# InkTimeSlay.net
KiCad netlist of a schematic drawn in EAGLE
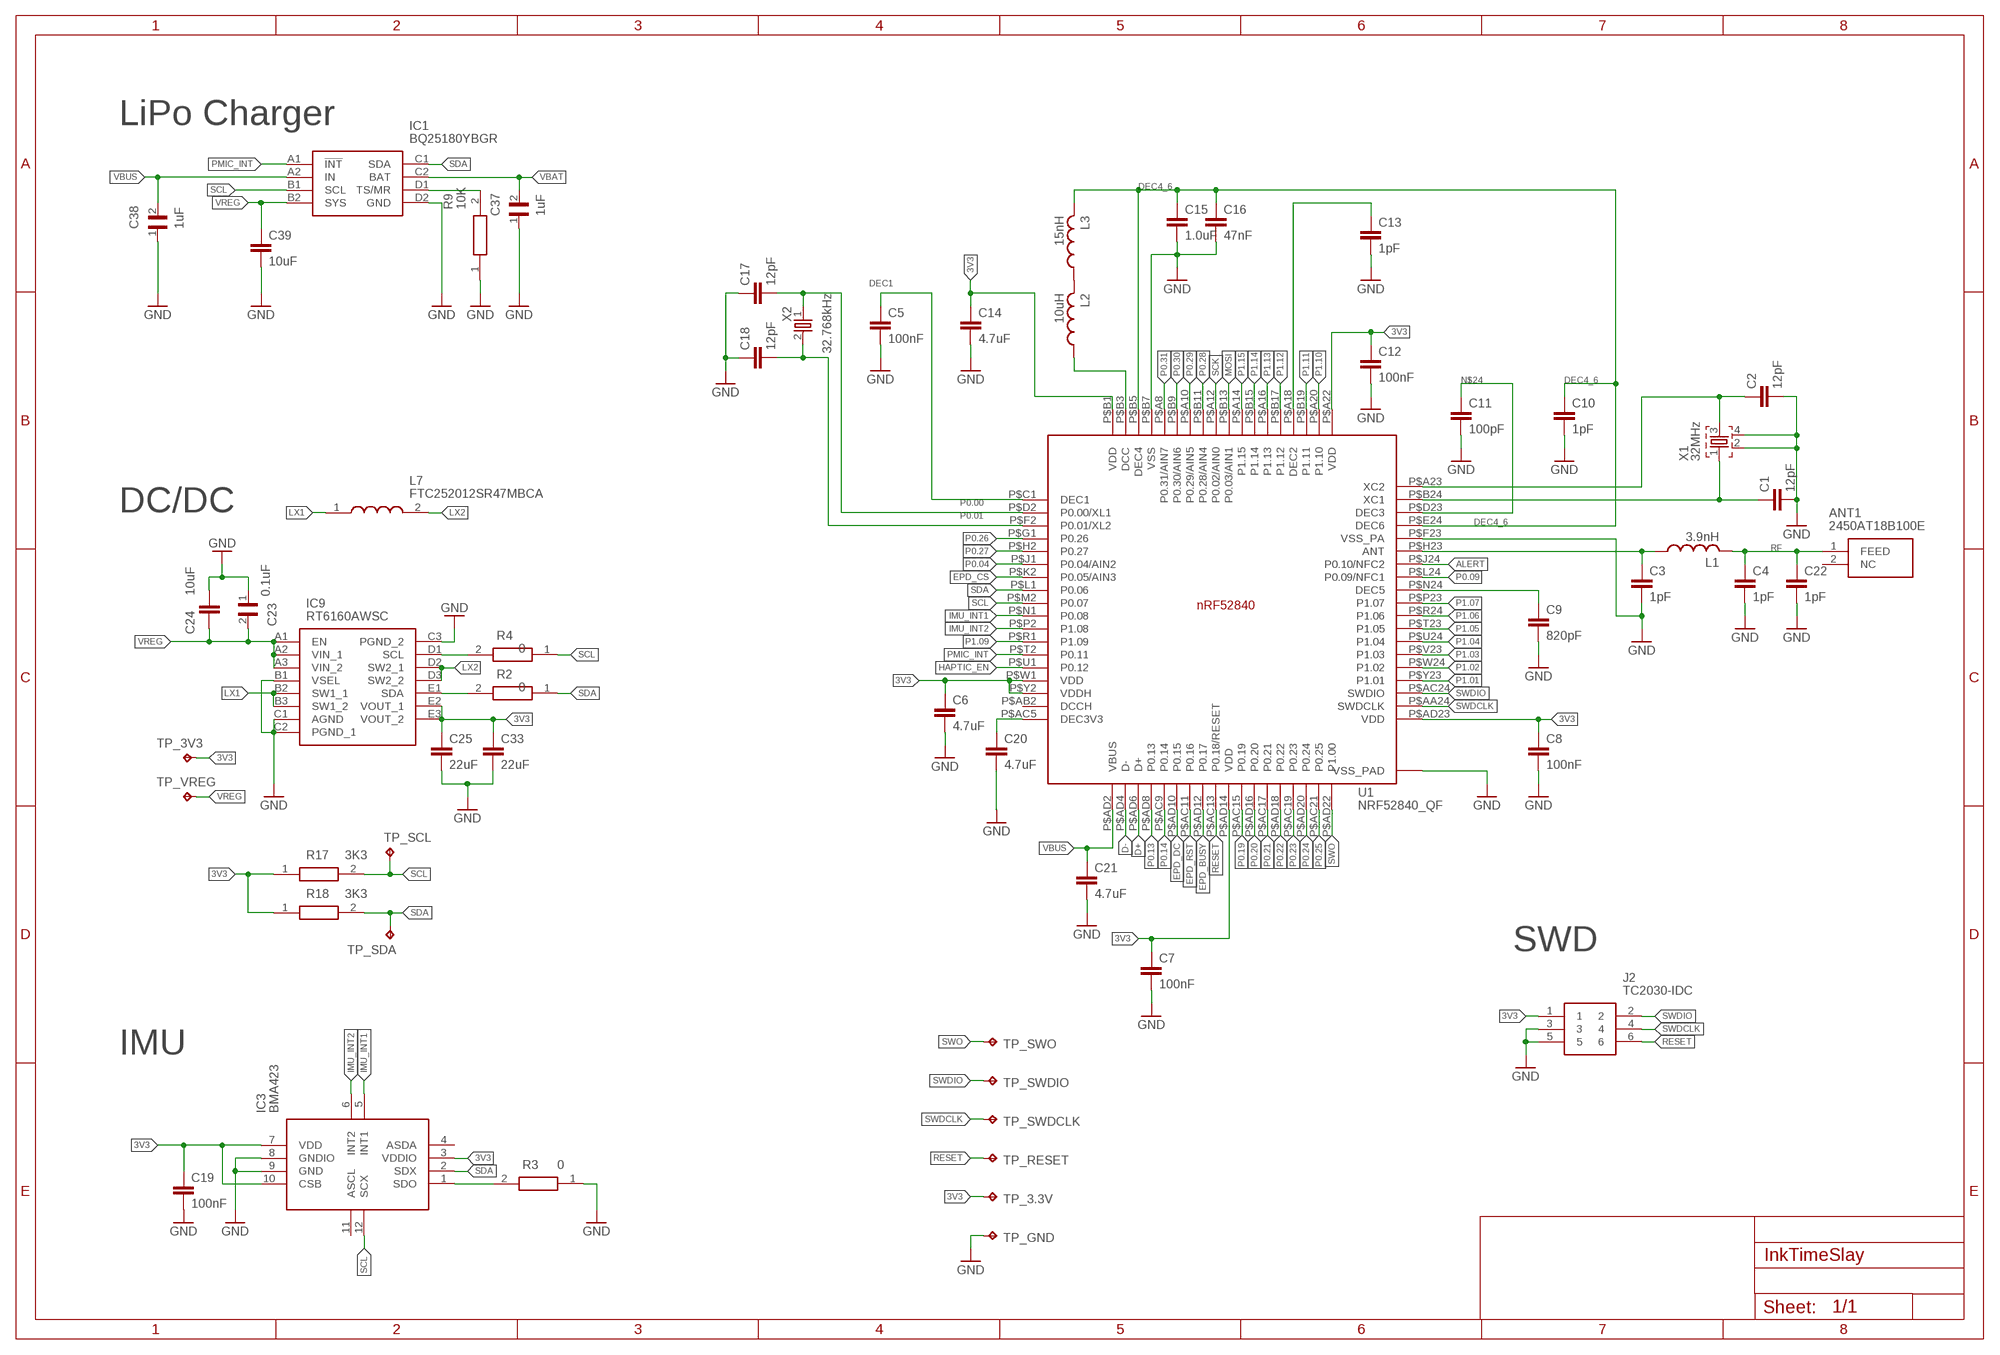
[diagram p0: schematic, sheet 1, part 1 of 2]
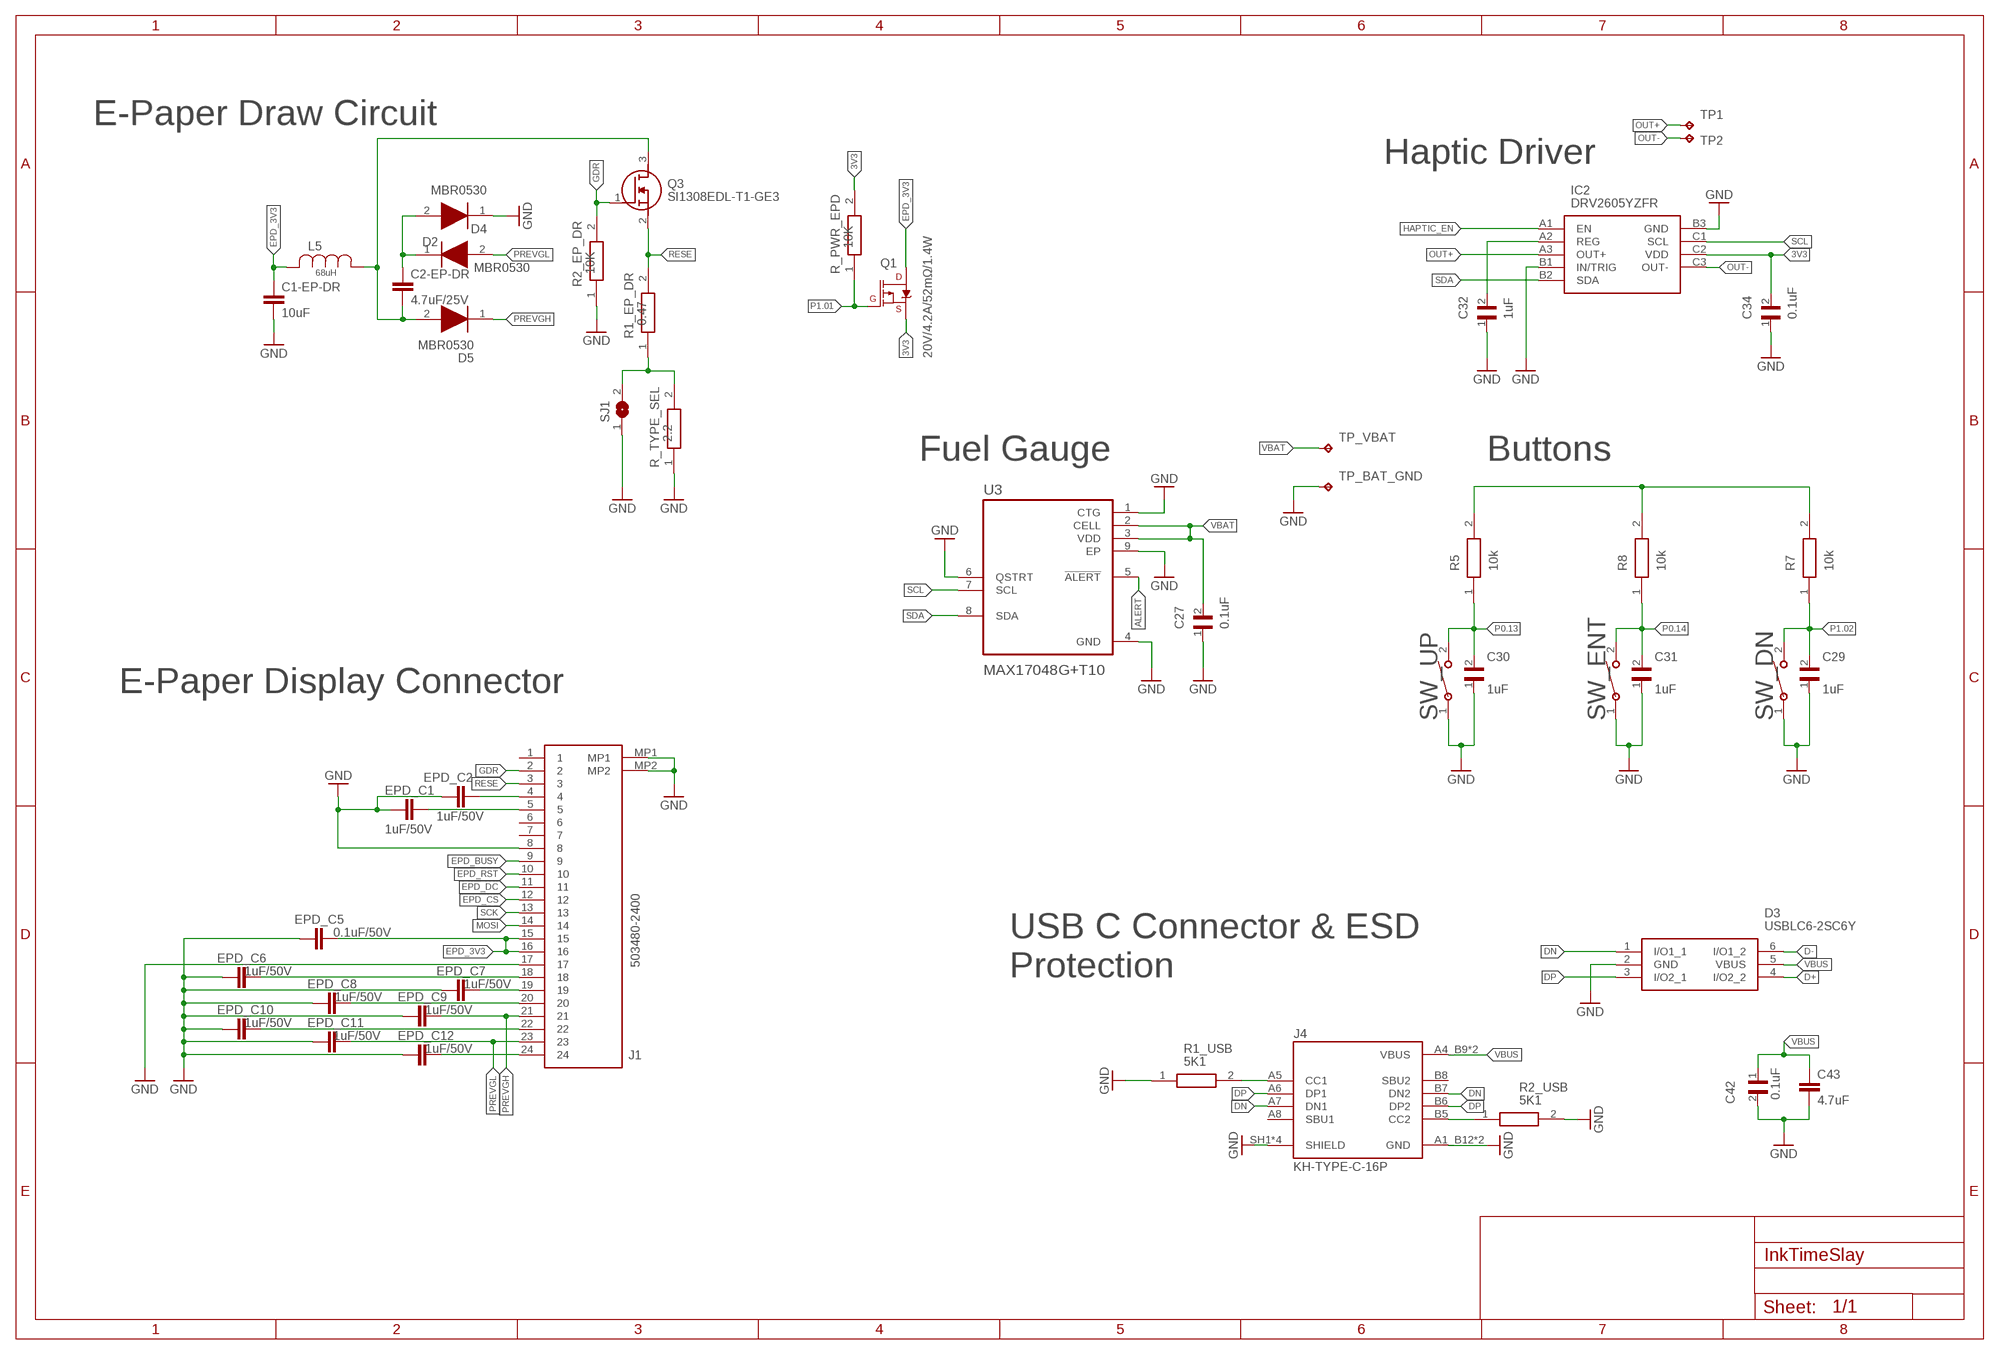
[diagram p1: schematic, sheet 1, part 2 of 2]

(export (version "E")
  (design (tool "Eeschema 10.0.6"))
  (components
    (comp (ref "ANT1")
      (value "2450AT18B100E")
      (footprint "eagle-import:2450AT18B100E_ANTC3216X140N")
      (fields (field (name "MOUSER_PART_NUMBER") "609-2450AT18B100E"))
      (libsource (lib "eagle-import") (part "2450AT18B100E_2450AT18B100E"))
    )
    (comp (ref "C1")
      (value "12pF")
      (footprint "eagle-import:NORDIC_NRF_3_RESC0201_L")
      (libsource (lib "eagle-import") (part "NORDIC_NRF_3_CAPACITOR_0201_L"))
    )
    (comp (ref "C1-EP-DR")
      (value "10uF")
      (footprint "eagle-import:NORDIC_NRF_3_RESC0402_L")
      (libsource (lib "eagle-import") (part "NORDIC_NRF_3_CAPACITOR_0402_L"))
    )
    (comp (ref "C2")
      (value "12pF")
      (footprint "eagle-import:NORDIC_NRF_3_RESC0201_L")
      (libsource (lib "eagle-import") (part "NORDIC_NRF_3_CAPACITOR_0201_L"))
    )
    (comp (ref "C2-EP-DR")
      (value "4.7uF/25V")
      (footprint "eagle-import:NORDIC_NRF_3_RESC0402_L")
      (libsource (lib "eagle-import") (part "NORDIC_NRF_3_CAPACITOR_0402_L"))
    )
    (comp (ref "C3")
      (value "1pF")
      (footprint "eagle-import:NORDIC_NRF_3_RESC0201_L")
      (libsource (lib "eagle-import") (part "NORDIC_NRF_3_CAPACITOR_0201_L"))
    )
    (comp (ref "C4")
      (value "1pF")
      (footprint "eagle-import:NORDIC_NRF_3_RESC0201_L")
      (libsource (lib "eagle-import") (part "NORDIC_NRF_3_CAPACITOR_0201_L"))
    )
    (comp (ref "C5")
      (value "100nF")
      (footprint "eagle-import:NORDIC_NRF_3_RESC0201_L")
      (libsource (lib "eagle-import") (part "NORDIC_NRF_3_CAPACITOR_0201_L"))
    )
    (comp (ref "C6")
      (value "4.7uF")
      (footprint "eagle-import:NORDIC_NRF_3_RESC0402_L")
      (libsource (lib "eagle-import") (part "NORDIC_NRF_3_CAPACITOR_0402_L"))
    )
    (comp (ref "C7")
      (value "100nF")
      (footprint "eagle-import:NORDIC_NRF_3_RESC0201_L")
      (libsource (lib "eagle-import") (part "NORDIC_NRF_3_CAPACITOR_0201_L"))
    )
    (comp (ref "C8")
      (value "100nF")
      (footprint "eagle-import:NORDIC_NRF_3_RESC0201_L")
      (libsource (lib "eagle-import") (part "NORDIC_NRF_3_CAPACITOR_0201_L"))
    )
    (comp (ref "C9")
      (value "820pF")
      (footprint "eagle-import:NORDIC_NRF_3_RESC0201_L")
      (libsource (lib "eagle-import") (part "NORDIC_NRF_3_CAPACITOR_0201_L"))
    )
    (comp (ref "C10")
      (value "1pF")
      (footprint "eagle-import:NORDIC_NRF_3_RESC0201_L")
      (libsource (lib "eagle-import") (part "NORDIC_NRF_3_CAPACITOR_0201_L"))
    )
    (comp (ref "C11")
      (value "100pF")
      (footprint "eagle-import:NORDIC_NRF_3_RESC0201_L")
      (libsource (lib "eagle-import") (part "NORDIC_NRF_3_CAPACITOR_0201_L"))
    )
    (comp (ref "C12")
      (value "100nF")
      (footprint "eagle-import:NORDIC_NRF_3_RESC0201_L")
      (libsource (lib "eagle-import") (part "NORDIC_NRF_3_CAPACITOR_0201_L"))
    )
    (comp (ref "C13")
      (value "1pF")
      (footprint "eagle-import:NORDIC_NRF_3_RESC0201_L")
      (libsource (lib "eagle-import") (part "NORDIC_NRF_3_CAPACITOR_0201_L"))
    )
    (comp (ref "C14")
      (value "4.7uF")
      (footprint "eagle-import:NORDIC_NRF_3_RESC0402_L")
      (libsource (lib "eagle-import") (part "NORDIC_NRF_3_CAPACITOR_0402_L"))
    )
    (comp (ref "C15")
      (value "1.0uF")
      (footprint "eagle-import:NORDIC_NRF_3_RESC0402_L")
      (libsource (lib "eagle-import") (part "NORDIC_NRF_3_CAPACITOR_0402_L"))
    )
    (comp (ref "C16")
      (value "47nF")
      (footprint "eagle-import:NORDIC_NRF_3_RESC0201_L")
      (libsource (lib "eagle-import") (part "NORDIC_NRF_3_CAPACITOR_0201_L"))
    )
    (comp (ref "C17")
      (value "12pF")
      (footprint "eagle-import:NORDIC_NRF_3_RESC0201_L")
      (libsource (lib "eagle-import") (part "NORDIC_NRF_3_CAPACITOR_0201_L"))
    )
    (comp (ref "C18")
      (value "12pF")
      (footprint "eagle-import:NORDIC_NRF_3_RESC0201_L")
      (libsource (lib "eagle-import") (part "NORDIC_NRF_3_CAPACITOR_0201_L"))
    )
    (comp (ref "C19")
      (value "100nF")
      (footprint "eagle-import:NORDIC_NRF_3_RESC0201_L")
      (libsource (lib "eagle-import") (part "NORDIC_NRF_3_CAPACITOR_0201_L"))
    )
    (comp (ref "C20")
      (value "4.7uF")
      (footprint "eagle-import:NORDIC_NRF_3_RESC0402_L")
      (libsource (lib "eagle-import") (part "NORDIC_NRF_3_CAPACITOR_0402_L"))
    )
    (comp (ref "C21")
      (value "4.7uF")
      (footprint "eagle-import:NORDIC_NRF_3_RESC0402_L")
      (libsource (lib "eagle-import") (part "NORDIC_NRF_3_CAPACITOR_0402_L"))
    )
    (comp (ref "C22")
      (value "1pF")
      (footprint "eagle-import:NORDIC_NRF_3_RESC0201_L")
      (libsource (lib "eagle-import") (part "NORDIC_NRF_3_CAPACITOR_0201_L"))
    )
    (comp (ref "C23")
      (value "0.1uF")
      (footprint "eagle-import:GRM011R60J152KE01L_2_CAPC0201X13N")
      (fields (field (name "MF") "Murata") (field (name "MP") "GRM011R60J152KE01L"))
      (libsource (lib "eagle-import") (part "GRM011R60J152KE01L_2_GRM011R60J152KE01L"))
    )
    (comp (ref "C24")
      (value "10uF")
      (footprint "eagle-import:NORDIC_NRF_3_RESC0402_L")
      (libsource (lib "eagle-import") (part "NORDIC_NRF_3_CAPACITOR_0402_L"))
    )
    (comp (ref "C25")
      (value "22uF")
      (footprint "eagle-import:NORDIC_NRF_3_RESC0402_L")
      (libsource (lib "eagle-import") (part "NORDIC_NRF_3_CAPACITOR_0402_L"))
    )
    (comp (ref "C27")
      (value "0.1uF")
      (footprint "eagle-import:GRM011R60J152KE01L_2_CAPC0201X13N")
      (fields (field (name "MF") "Murata") (field (name "MP") "GRM011R60J152KE01L"))
      (libsource (lib "eagle-import") (part "GRM011R60J152KE01L_2_GRM011R60J152KE01L"))
    )
    (comp (ref "C29")
      (value "1uF")
      (footprint "eagle-import:GRM011R60J152KE01L_2_CAPC0201X13N")
      (fields (field (name "MF") "Murata") (field (name "MP") "GRM011R60J152KE01L"))
      (libsource (lib "eagle-import") (part "GRM011R60J152KE01L_2_GRM011R60J152KE01L"))
    )
    (comp (ref "C30")
      (value "1uF")
      (footprint "eagle-import:GRM011R60J152KE01L_2_CAPC0201X13N")
      (fields (field (name "MF") "Murata") (field (name "MP") "GRM011R60J152KE01L"))
      (libsource (lib "eagle-import") (part "GRM011R60J152KE01L_2_GRM011R60J152KE01L"))
    )
    (comp (ref "C31")
      (value "1uF")
      (footprint "eagle-import:GRM011R60J152KE01L_2_CAPC0201X13N")
      (fields (field (name "MF") "Murata") (field (name "MP") "GRM011R60J152KE01L"))
      (libsource (lib "eagle-import") (part "GRM011R60J152KE01L_2_GRM011R60J152KE01L"))
    )
    (comp (ref "C32")
      (value "1uF")
      (footprint "eagle-import:GRM011R60J152KE01L_2_CAPC0201X13N")
      (fields (field (name "MF") "Murata") (field (name "MP") "GRM011R60J152KE01L"))
      (libsource (lib "eagle-import") (part "GRM011R60J152KE01L_2_GRM011R60J152KE01L"))
    )
    (comp (ref "C33")
      (value "22uF")
      (footprint "eagle-import:NORDIC_NRF_3_RESC0402_L")
      (libsource (lib "eagle-import") (part "NORDIC_NRF_3_CAPACITOR_0402_L"))
    )
    (comp (ref "C34")
      (value "0.1uF")
      (footprint "eagle-import:GRM011R60J152KE01L_2_CAPC0201X13N")
      (fields (field (name "MF") "Murata") (field (name "MP") "GRM011R60J152KE01L"))
      (libsource (lib "eagle-import") (part "GRM011R60J152KE01L_2_GRM011R60J152KE01L"))
    )
    (comp (ref "C37")
      (value "1uF")
      (footprint "eagle-import:GRM011R60J152KE01L_2_CAPC0201X13N")
      (fields (field (name "MF") "Murata") (field (name "MP") "GRM011R60J152KE01L"))
      (libsource (lib "eagle-import") (part "GRM011R60J152KE01L_2_GRM011R60J152KE01L"))
    )
    (comp (ref "C38")
      (value "1uF")
      (footprint "eagle-import:GRM011R60J152KE01L_2_CAPC0201X13N")
      (fields (field (name "MF") "Murata") (field (name "MP") "GRM011R60J152KE01L"))
      (libsource (lib "eagle-import") (part "GRM011R60J152KE01L_2_GRM011R60J152KE01L"))
    )
    (comp (ref "C39")
      (value "10uF")
      (footprint "eagle-import:NORDIC_NRF_3_RESC0402_L")
      (libsource (lib "eagle-import") (part "NORDIC_NRF_3_CAPACITOR_0402_L"))
    )
    (comp (ref "C42")
      (value "0.1uF")
      (footprint "eagle-import:GRM011R60J152KE01L_2_CAPC0201X13N")
      (fields (field (name "MF") "Murata") (field (name "MP") "GRM011R60J152KE01L"))
      (libsource (lib "eagle-import") (part "GRM011R60J152KE01L_2_GRM011R60J152KE01L"))
    )
    (comp (ref "C43")
      (value "4.7uF")
      (footprint "eagle-import:NORDIC_NRF_3_RESC0402_L")
      (libsource (lib "eagle-import") (part "NORDIC_NRF_3_CAPACITOR_0402_L"))
    )
    (comp (ref "D2")
      (value "MBR0530")
      (footprint "eagle-import:ESP32_C6_LIBRARY_5_SOD3716X135N")
      (fields (field (name "MF") "ON Semiconductor"))
      (libsource (lib "eagle-import") (part "ESP32_C6_LIBRARY_5_MBR0530"))
    )
    (comp (ref "D3")
      (value "USBLC6-2SC6Y")
      (footprint "eagle-import:ESP32_C6_LIBRARY_3_SOT95P280X145-6N")
      (fields (field (name "MF") "STMicroelectronics"))
      (libsource (lib "eagle-import") (part "ESP32_C6_LIBRARY_3_USBLC6-2SC6Y"))
    )
    (comp (ref "D4")
      (value "MBR0530")
      (footprint "eagle-import:ESP32_C6_LIBRARY_5_SOD3716X135N")
      (fields (field (name "MF") "ON Semiconductor"))
      (libsource (lib "eagle-import") (part "ESP32_C6_LIBRARY_5_MBR0530"))
    )
    (comp (ref "D5")
      (value "MBR0530")
      (footprint "eagle-import:ESP32_C6_LIBRARY_5_SOD3716X135N")
      (fields (field (name "MF") "ON Semiconductor"))
      (libsource (lib "eagle-import") (part "ESP32_C6_LIBRARY_5_MBR0530"))
    )
    (comp (ref "EPD_C1")
      (value "1uF/50V")
      (footprint "eagle-import:NORDIC_NRF_3_RESC0402_L")
      (libsource (lib "eagle-import") (part "NORDIC_NRF_3_CAPACITOR_0402_L"))
    )
    (comp (ref "EPD_C2")
      (value "1uF/50V")
      (footprint "eagle-import:NORDIC_NRF_3_RESC0402_L")
      (libsource (lib "eagle-import") (part "NORDIC_NRF_3_CAPACITOR_0402_L"))
    )
    (comp (ref "EPD_C5")
      (value "0.1uF/50V")
      (footprint "eagle-import:NORDIC_NRF_3_RESC0201_L")
      (libsource (lib "eagle-import") (part "NORDIC_NRF_3_CAPACITOR_0201_L"))
    )
    (comp (ref "EPD_C6")
      (value "1uF/50V")
      (footprint "eagle-import:NORDIC_NRF_3_RESC0402_L")
      (libsource (lib "eagle-import") (part "NORDIC_NRF_3_CAPACITOR_0402_L"))
    )
    (comp (ref "EPD_C7")
      (value "1uF/50V")
      (footprint "eagle-import:NORDIC_NRF_3_RESC0402_L")
      (libsource (lib "eagle-import") (part "NORDIC_NRF_3_CAPACITOR_0402_L"))
    )
    (comp (ref "EPD_C8")
      (value "1uF/50V")
      (footprint "eagle-import:NORDIC_NRF_3_RESC0402_L")
      (libsource (lib "eagle-import") (part "NORDIC_NRF_3_CAPACITOR_0402_L"))
    )
    (comp (ref "EPD_C9")
      (value "1uF/50V")
      (footprint "eagle-import:NORDIC_NRF_3_RESC0402_L")
      (libsource (lib "eagle-import") (part "NORDIC_NRF_3_CAPACITOR_0402_L"))
    )
    (comp (ref "EPD_C10")
      (value "1uF/50V")
      (footprint "eagle-import:NORDIC_NRF_3_RESC0402_L")
      (libsource (lib "eagle-import") (part "NORDIC_NRF_3_CAPACITOR_0402_L"))
    )
    (comp (ref "EPD_C11")
      (value "1uF/50V")
      (footprint "eagle-import:NORDIC_NRF_3_RESC0402_L")
      (libsource (lib "eagle-import") (part "NORDIC_NRF_3_CAPACITOR_0402_L"))
    )
    (comp (ref "EPD_C12")
      (value "1uF/50V")
      (footprint "eagle-import:NORDIC_NRF_3_RESC0402_L")
      (libsource (lib "eagle-import") (part "NORDIC_NRF_3_CAPACITOR_0402_L"))
    )
    (comp (ref "IC1")
      (value "BQ25180YBGR")
      (footprint "eagle-import:BQ25180YBGR_BGA8C40P2X4_100X155X50")
      (fields (field (name "MOUSER_PART_NUMBER") "595-BQ25180YBGR"))
      (libsource (lib "eagle-import") (part "BQ25180YBGR_BQ25180YBGR"))
    )
    (comp (ref "IC2")
      (value "DRV2605YZFR")
      (footprint "eagle-import:DRV2605YZFR_BGA9C50P3X3_144X144X62")
      (libsource (lib "eagle-import") (part "DRV2605YZFR_DRV2605YZFR"))
    )
    (comp (ref "IC3")
      (value "BMA423")
      (footprint "eagle-import:BMA423_BMA423")
      (fields (field (name "MOUSER_PART_NUMBER") "262-BMA423"))
      (libsource (lib "eagle-import") (part "BMA423_BMA423"))
    )
    (comp (ref "IC9")
      (value "RT6160AWSC")
      (footprint "eagle-import:RT6160AWSC_BGA15C40P3X5_140X230X60")
      (fields (field (name "MOUSER_PART_NUMBER") "835-RT6160AWSC"))
      (libsource (lib "eagle-import") (part "RT6160AWSC_RT6160AWSC"))
    )
    (comp (ref "J1")
      (value "503480-2400")
      (footprint "eagle-import:503480-2400_5034802400")
      (fields (field (name "MOUSER_PART_NUMBER") "538-503480-2400"))
      (libsource (lib "eagle-import") (part "503480-2400_503480-2400"))
    )
    (comp (ref "J2")
      (value "TC2030-IDC")
      (footprint "eagle-import:TC2030-IDC_TC2030IDC")
      (libsource (lib "eagle-import") (part "TC2030-IDC_TC2030-IDC"))
    )
    (comp (ref "J4")
      (value "KH-TYPE-C-16P")
      (footprint "eagle-import:KH-TYPE-C-16P_KINGHELM_KH-TYPE-C-16P")
      (fields (field (name "MF") "kinghelm"))
      (libsource (lib "eagle-import") (part "KH-TYPE-C-16P_KH-TYPE-C-16P"))
    )
    (comp (ref "L1")
      (value "3.9nH")
      (footprint "eagle-import:NORDIC_NRF_2_RESC0402_L")
      (libsource (lib "eagle-import") (part "NORDIC_NRF_2_INDUCTOR_0402_L"))
    )
    (comp (ref "L2")
      (value "10uH")
      (footprint "eagle-import:NORDIC_NRF_2_RESC0402_L")
      (libsource (lib "eagle-import") (part "NORDIC_NRF_2_INDUCTOR_0402_L"))
    )
    (comp (ref "L3")
      (value "15nH")
      (footprint "eagle-import:NORDIC_NRF_2_RESC0402_L")
      (libsource (lib "eagle-import") (part "NORDIC_NRF_2_INDUCTOR_0402_L"))
    )
    (comp (ref "L5")
      (value "68uH")
      (footprint "eagle-import:ESP32_C6_LIBRARY_2_IND_4828-WE-TPC_WRE")
      (fields
        (field (name "MANUFACTURER_PART_NUMBER") "744043680")
        (field (name "COPYRIGHT") "Copyright (C) 2024 Ultra Librarian. All rights reserved.")
      )
      (libsource (lib "eagle-import") (part "ESP32_C6_LIBRARY_2_744043680IND_4828-WE-TPC_WRE"))
    )
    (comp (ref "L7")
      (value "FTC252012SR47MBCA")
      (footprint "eagle-import:MLP2016SR47MT0S1_INDC2016X100N")
      (libsource (lib "eagle-import") (part "MLP2016SR47MT0S1_FTC252012SR47MBCA"))
    )
    (comp (ref "Q1")
      (value "20V/4.2A/52mΩ/1.4W")
      (footprint "eagle-import:ESP32_C6_LIBRARY_4_ESP32_C6_LIBRARY_4_ESP32_C6_LIBRARY_4_ESP32_C6_LIBRARY_4_ESP32_WROVER_SPARKFUN-DISCRETESEMI_SOT23-3")
      (libsource (lib "eagle-import") (part "ESP32_C6_LIBRARY_4_ESP32_WROVER_SPARKFUN-DISCRETESEMI_MOSFET_PCH-DMG2305UX-7"))
    )
    (comp (ref "Q3")
      (value "SI1308EDL-T1-GE3")
      (footprint "eagle-import:ESP32_C6_LIBRARY_6_SOT65P210X110-3N")
      (fields (field (name "MF") "Vishay Siliconix"))
      (libsource (lib "eagle-import") (part "ESP32_C6_LIBRARY_6_SI1308EDL-T1-GE3"))
    )
    (comp (ref "R1_EP_DR")
      (value "0.47")
      (footprint "eagle-import:ERA-1AEB3401C_0201")
      (libsource (lib "eagle-import") (part "ERA-1AEB3401C_CPF0201D7K68C1"))
    )
    (comp (ref "R1_USB")
      (value "5K1")
      (footprint "eagle-import:ERA-1AEB3401C_0201")
      (libsource (lib "eagle-import") (part "ERA-1AEB3401C_CPF0201D7K68C1"))
    )
    (comp (ref "R2")
      (value "0")
      (footprint "eagle-import:ERA-1AEB3401C_0201")
      (libsource (lib "eagle-import") (part "ERA-1AEB3401C_CPF0201D7K68C1"))
    )
    (comp (ref "R2_EP_DR")
      (value "10K")
      (footprint "eagle-import:ERA-1AEB3401C_0201")
      (libsource (lib "eagle-import") (part "ERA-1AEB3401C_CPF0201D7K68C1"))
    )
    (comp (ref "R2_USB")
      (value "5K1")
      (footprint "eagle-import:ERA-1AEB3401C_0201")
      (libsource (lib "eagle-import") (part "ERA-1AEB3401C_CPF0201D7K68C1"))
    )
    (comp (ref "R3")
      (value "0")
      (footprint "eagle-import:ERA-1AEB3401C_0201")
      (libsource (lib "eagle-import") (part "ERA-1AEB3401C_CPF0201D7K68C1"))
    )
    (comp (ref "R4")
      (value "0")
      (footprint "eagle-import:ERA-1AEB3401C_0201")
      (libsource (lib "eagle-import") (part "ERA-1AEB3401C_CPF0201D7K68C1"))
    )
    (comp (ref "R5")
      (value "10k")
      (footprint "eagle-import:ERA-1AEB3401C_0201")
      (libsource (lib "eagle-import") (part "ERA-1AEB3401C_CPF0201D7K68C1"))
    )
    (comp (ref "R7")
      (value "10k")
      (footprint "eagle-import:ERA-1AEB3401C_0201")
      (libsource (lib "eagle-import") (part "ERA-1AEB3401C_CPF0201D7K68C1"))
    )
    (comp (ref "R8")
      (value "10k")
      (footprint "eagle-import:ERA-1AEB3401C_0201")
      (libsource (lib "eagle-import") (part "ERA-1AEB3401C_CPF0201D7K68C1"))
    )
    (comp (ref "R9")
      (value "10K")
      (footprint "eagle-import:ERA-1AEB3401C_0201")
      (libsource (lib "eagle-import") (part "ERA-1AEB3401C_CPF0201D7K68C1"))
    )
    (comp (ref "R17")
      (value "3K3")
      (footprint "eagle-import:ERA-1AEB3401C_0201")
      (libsource (lib "eagle-import") (part "ERA-1AEB3401C_CPF0201D7K68C1"))
    )
    (comp (ref "R18")
      (value "3K3")
      (footprint "eagle-import:ERA-1AEB3401C_0201")
      (libsource (lib "eagle-import") (part "ERA-1AEB3401C_CPF0201D7K68C1"))
    )
    (comp (ref "R_PWR_EPD")
      (value "10K")
      (footprint "eagle-import:ERA-1AEB3401C_0201")
      (libsource (lib "eagle-import") (part "ERA-1AEB3401C_CPF0201D7K68C1"))
    )
    (comp (ref "R_TYPE_SEL")
      (value "2.2")
      (footprint "eagle-import:ERA-1AEB3401C_0201")
      (libsource (lib "eagle-import") (part "ERA-1AEB3401C_CPF0201D7K68C1"))
    )
    (comp (ref "SJ1")
      (value "ESP32_C6_LIBRARY_7_JUMPER_SJ")
      (footprint "eagle-import:ESP32_C6_LIBRARY_7_JUMPER_SJ")
      (libsource (lib "eagle-import") (part "ESP32_C6_LIBRARY_7_JUMPER_SJ"))
    )
    (comp (ref "SW_DN")
      (value "2025-10-22_07-23-44_LIBRARY_EVP-AKE31ASW_EVP-AKE31A_PAN")
      (footprint "eagle-import:2025-10-22_07-23-44_LIBRARY_SW_EVP-AKE31A_PAN")
      (fields
        (field (name "MANUFACTURER_PART_NUMBER") "EVP-AKE31A")
        (field (name "COPYRIGHT") "Copyright (C) 2025 Ultra Librarian. All rights reserved.")
      )
      (libsource (lib "eagle-import") (part "2025-10-22_07-23-44_LIBRARY_EVP-AKE31ASW_EVP-AKE31A_PAN"))
    )
    (comp (ref "SW_ENT")
      (value "2025-10-22_07-23-44_LIBRARY_EVP-AKE31ASW_EVP-AKE31A_PAN")
      (footprint "eagle-import:2025-10-22_07-23-44_LIBRARY_SW_EVP-AKE31A_PAN")
      (fields
        (field (name "MANUFACTURER_PART_NUMBER") "EVP-AKE31A")
        (field (name "COPYRIGHT") "Copyright (C) 2025 Ultra Librarian. All rights reserved.")
      )
      (libsource (lib "eagle-import") (part "2025-10-22_07-23-44_LIBRARY_EVP-AKE31ASW_EVP-AKE31A_PAN"))
    )
    (comp (ref "SW_UP")
      (value "2025-10-22_07-23-44_LIBRARY_EVP-AKE31ASW_EVP-AKE31A_PAN")
      (footprint "eagle-import:2025-10-22_07-23-44_LIBRARY_SW_EVP-AKE31A_PAN")
      (fields
        (field (name "MANUFACTURER_PART_NUMBER") "EVP-AKE31A")
        (field (name "COPYRIGHT") "Copyright (C) 2025 Ultra Librarian. All rights reserved.")
      )
      (libsource (lib "eagle-import") (part "2025-10-22_07-23-44_LIBRARY_EVP-AKE31ASW_EVP-AKE31A_PAN"))
    )
    (comp (ref "TP1")
      (value "HECTOR_WATCH_1_TPTP20R")
      (footprint "eagle-import:HECTOR_WATCH_1_TP20R")
      (libsource (lib "eagle-import") (part "HECTOR_WATCH_1_TPTP20R"))
    )
    (comp (ref "TP2")
      (value "HECTOR_WATCH_1_TPTP20R")
      (footprint "eagle-import:HECTOR_WATCH_1_TP20R")
      (libsource (lib "eagle-import") (part "HECTOR_WATCH_1_TPTP20R"))
    )
    (comp (ref "TP_3.3V")
      (value "HECTOR_WATCH_1_TPTP20R")
      (footprint "eagle-import:HECTOR_WATCH_1_TP20R")
      (libsource (lib "eagle-import") (part "HECTOR_WATCH_1_TPTP20R"))
    )
    (comp (ref "TP_3V3")
      (value "HECTOR_WATCH_1_TPTP20R")
      (footprint "eagle-import:HECTOR_WATCH_1_TP20R")
      (libsource (lib "eagle-import") (part "HECTOR_WATCH_1_TPTP20R"))
    )
    (comp (ref "TP_BAT_GND")
      (value "HECTOR_WATCH_1_TPTP20R")
      (footprint "eagle-import:HECTOR_WATCH_1_TP20R")
      (libsource (lib "eagle-import") (part "HECTOR_WATCH_1_TPTP20R"))
    )
    (comp (ref "TP_GND")
      (value "HECTOR_WATCH_1_TPTP20R")
      (footprint "eagle-import:HECTOR_WATCH_1_TP20R")
      (libsource (lib "eagle-import") (part "HECTOR_WATCH_1_TPTP20R"))
    )
    (comp (ref "TP_RESET")
      (value "HECTOR_WATCH_1_TPTP20R")
      (footprint "eagle-import:HECTOR_WATCH_1_TP20R")
      (libsource (lib "eagle-import") (part "HECTOR_WATCH_1_TPTP20R"))
    )
    (comp (ref "TP_SCL")
      (value "HECTOR_WATCH_1_TPTP20R")
      (footprint "eagle-import:HECTOR_WATCH_1_TP20R")
      (libsource (lib "eagle-import") (part "HECTOR_WATCH_1_TPTP20R"))
    )
    (comp (ref "TP_SDA")
      (value "HECTOR_WATCH_1_TPTP20R")
      (footprint "eagle-import:HECTOR_WATCH_1_TP20R")
      (libsource (lib "eagle-import") (part "HECTOR_WATCH_1_TPTP20R"))
    )
    (comp (ref "TP_SWDCLK")
      (value "HECTOR_WATCH_1_TPTP20R")
      (footprint "eagle-import:HECTOR_WATCH_1_TP20R")
      (libsource (lib "eagle-import") (part "HECTOR_WATCH_1_TPTP20R"))
    )
    (comp (ref "TP_SWDIO")
      (value "HECTOR_WATCH_1_TPTP20R")
      (footprint "eagle-import:HECTOR_WATCH_1_TP20R")
      (libsource (lib "eagle-import") (part "HECTOR_WATCH_1_TPTP20R"))
    )
    (comp (ref "TP_SWO")
      (value "HECTOR_WATCH_1_TPTP20R")
      (footprint "eagle-import:HECTOR_WATCH_1_TP20R")
      (libsource (lib "eagle-import") (part "HECTOR_WATCH_1_TPTP20R"))
    )
    (comp (ref "TP_VBAT")
      (value "HECTOR_WATCH_1_TPTP20R")
      (footprint "eagle-import:HECTOR_WATCH_1_TP20R")
      (libsource (lib "eagle-import") (part "HECTOR_WATCH_1_TPTP20R"))
    )
    (comp (ref "TP_VREG")
      (value "HECTOR_WATCH_1_TPTP20R")
      (footprint "eagle-import:HECTOR_WATCH_1_TP20R")
      (libsource (lib "eagle-import") (part "HECTOR_WATCH_1_TPTP20R"))
    )
    (comp (ref "U1")
      (value "NRF52840_QF")
      (footprint "eagle-import:NORDIC_NRF_4_AQFN50P700X700X85_HS-74N")
      (libsource (lib "eagle-import") (part "NORDIC_NRF_4_NRF52840_QF"))
    )
    (comp (ref "U3")
      (value "MAX17048G+T10")
      (footprint "eagle-import:ESP32_C6_LIBRARY_SON50P200X200X80-9N")
      (fields (field (name "MF") "Analog Devices"))
      (libsource (lib "eagle-import") (part "ESP32_C6_LIBRARY_MAX17048G+T10"))
    )
    (comp (ref "X1")
      (value "32MHz")
      (footprint "eagle-import:NORDIC_NRF_BT-XTAL_2016_N")
      (libsource (lib "eagle-import") (part "NORDIC_NRF_XTAL_32MHZ"))
    )
    (comp (ref "X2")
      (value "32.768kHz")
      (footprint "eagle-import:NORDIC_NRF_1_XTAL_3215_N")
      (libsource (lib "eagle-import") (part "NORDIC_NRF_1_XTAL_32KHZ"))
    )
  )
  (nets
    (net (code "1") (name "/DEC1") (class "Default")
      (node (ref "C5") (pin "1") (pinfunction "1_1") (pintype "passive"))
      (node (ref "U1") (pin "P$C1") (pinfunction "DEC1_P$C1") (pintype "power_in"))
    )
    (net (code "2") (name "/DEC4_6") (class "Default")
      (node (ref "C10") (pin "1") (pinfunction "1_1") (pintype "passive"))
      (node (ref "C15") (pin "1") (pinfunction "1_1") (pintype "passive"))
      (node (ref "C16") (pin "1") (pinfunction "1_1") (pintype "passive"))
      (node (ref "L3") (pin "2") (pinfunction "2_2") (pintype "passive"))
      (node (ref "U1") (pin "P$B5") (pinfunction "DEC4_P$B5") (pintype "power_in"))
      (node (ref "U1") (pin "P$E24") (pinfunction "DEC6_P$E24") (pintype "bidirectional"))
    )
    (net (code "3") (name "/N$24") (class "Default")
      (node (ref "C11") (pin "1") (pinfunction "1_1") (pintype "passive"))
      (node (ref "U1") (pin "P$D23") (pinfunction "DEC3_P$D23") (pintype "bidirectional"))
    )
    (net (code "4") (name "/P0.00") (class "Default")
      (node (ref "C17") (pin "2") (pinfunction "2_2") (pintype "passive"))
      (node (ref "U1") (pin "P$D2") (pinfunction "P0.00/XL1_P$D2") (pintype "bidirectional"))
      (node (ref "X2") (pin "1") (pinfunction "1_1") (pintype "passive"))
    )
    (net (code "5") (name "/P0.01") (class "Default")
      (node (ref "C18") (pin "2") (pinfunction "2_2") (pintype "passive"))
      (node (ref "U1") (pin "P$F2") (pinfunction "P0.01/XL2_P$F2") (pintype "bidirectional"))
      (node (ref "X2") (pin "2") (pinfunction "2_2") (pintype "passive"))
    )
    (net (code "6") (name "/RF") (class "Default")
      (node (ref "ANT1") (pin "1") (pinfunction "FEED_1") (pintype "input"))
      (node (ref "C22") (pin "1") (pinfunction "1_1") (pintype "passive"))
      (node (ref "C4") (pin "1") (pinfunction "1_1") (pintype "passive"))
      (node (ref "L1") (pin "2") (pinfunction "2_2") (pintype "passive"))
    )
    (net (code "7") (name "3V3") (class "Default")
      (node (ref "C12") (pin "1") (pinfunction "1_1") (pintype "passive"))
      (node (ref "C14") (pin "1") (pinfunction "1_1") (pintype "passive"))
      (node (ref "C19") (pin "1") (pinfunction "1_1") (pintype "passive"))
      (node (ref "C25") (pin "1") (pinfunction "1_1") (pintype "passive"))
      (node (ref "C33") (pin "1") (pinfunction "1_1") (pintype "passive"))
      (node (ref "C34") (pin "2") (pinfunction "2_2") (pintype "passive"))
      (node (ref "C6") (pin "1") (pinfunction "1_1") (pintype "passive"))
      (node (ref "C7") (pin "1") (pinfunction "1_1") (pintype "passive"))
      (node (ref "C8") (pin "1") (pinfunction "1_1") (pintype "passive"))
      (node (ref "IC2") (pin "C2") (pinfunction "VDD_C2") (pintype "bidirectional"))
      (node (ref "IC3") (pin "10") (pinfunction "CSB_10") (pintype "bidirectional"))
      (node (ref "IC3") (pin "3") (pinfunction "VDDIO_3") (pintype "bidirectional"))
      (node (ref "IC3") (pin "7") (pinfunction "VDD_7") (pintype "bidirectional"))
      (node (ref "IC9") (pin "E2") (pinfunction "VOUT_1_E2") (pintype "bidirectional"))
      (node (ref "IC9") (pin "E3") (pinfunction "VOUT_2_E3") (pintype "bidirectional"))
      (node (ref "J2") (pin "1") (pinfunction "1_1") (pintype "bidirectional"))
      (node (ref "Q1") (pin "2") (pinfunction "S_2") (pintype "bidirectional"))
      (node (ref "R17") (pin "1") (pinfunction "1_1") (pintype "bidirectional"))
      (node (ref "R18") (pin "1") (pinfunction "1_1") (pintype "bidirectional"))
      (node (ref "R_PWR_EPD") (pin "2") (pinfunction "2_2") (pintype "bidirectional"))
      (node (ref "TP_3.3V") (pin "TP") (pinfunction "TP_TP") (pintype "input"))
      (node (ref "TP_3V3") (pin "TP") (pinfunction "TP_TP") (pintype "input"))
      (node (ref "U1") (pin "P$A22") (pinfunction "VDD_P$A22") (pintype "power_in"))
      (node (ref "U1") (pin "P$AD14") (pinfunction "VDD_P$AD14") (pintype "power_in"))
      (node (ref "U1") (pin "P$AD23") (pinfunction "VDD_P$AD23") (pintype "power_in"))
      (node (ref "U1") (pin "P$B1") (pinfunction "VDD_P$B1") (pintype "power_in"))
      (node (ref "U1") (pin "P$W1") (pinfunction "VDD_P$W1") (pintype "power_in"))
      (node (ref "U1") (pin "P$Y2") (pinfunction "VDDH_P$Y2") (pintype "power_in"))
    )
    (net (code "8") (name "ALERT") (class "Default")
      (node (ref "U1") (pin "P$J24") (pinfunction "P0.10/NFC2_P$J24") (pintype "bidirectional"))
      (node (ref "U3") (pin "5") (pinfunction "~{ALERT}_5") (pintype "output"))
    )
    (net (code "9") (name "D+") (class "Default")
      (node (ref "D3") (pin "4") (pinfunction "I/O2_2_4") (pintype "bidirectional"))
      (node (ref "U1") (pin "P$AD6") (pinfunction "D+_P$AD6") (pintype "bidirectional"))
    )
    (net (code "10") (name "D-") (class "Default")
      (node (ref "D3") (pin "6") (pinfunction "I/O1_2_6") (pintype "bidirectional"))
      (node (ref "U1") (pin "P$AD4") (pinfunction "D-_P$AD4") (pintype "bidirectional"))
    )
    (net (code "11") (name "DN") (class "Default")
      (node (ref "D3") (pin "1") (pinfunction "I/O1_1_1") (pintype "bidirectional"))
      (node (ref "J4") (pin "A7") (pinfunction "DN1_A7") (pintype "bidirectional"))
      (node (ref "J4") (pin "B7") (pinfunction "DN2_B7") (pintype "bidirectional"))
    )
    (net (code "12") (name "DP") (class "Default")
      (node (ref "D3") (pin "3") (pinfunction "I/O2_1_3") (pintype "bidirectional"))
      (node (ref "J4") (pin "A6") (pinfunction "DP1_A6") (pintype "bidirectional"))
      (node (ref "J4") (pin "B6") (pinfunction "DP2_B6") (pintype "bidirectional"))
    )
    (net (code "13") (name "EPD_3V3") (class "Default")
      (node (ref "C1-EP-DR") (pin "1") (pinfunction "1_1") (pintype "passive"))
      (node (ref "EPD_C5") (pin "2") (pinfunction "2_2") (pintype "passive"))
      (node (ref "J1") (pin "15") (pinfunction "15_15") (pintype "bidirectional"))
      (node (ref "J1") (pin "16") (pinfunction "16_16") (pintype "bidirectional"))
      (node (ref "L5") (pin "2") (pinfunction "2_2") (pintype "passive"))
      (node (ref "Q1") (pin "3") (pinfunction "D_3") (pintype "bidirectional"))
    )
    (net (code "14") (name "EPD_BUSY") (class "Default")
      (node (ref "J1") (pin "9") (pinfunction "9_9") (pintype "bidirectional"))
      (node (ref "U1") (pin "P$AD12") (pinfunction "P0.17_P$AD12") (pintype "bidirectional"))
    )
    (net (code "15") (name "EPD_CS") (class "Default")
      (node (ref "J1") (pin "12") (pinfunction "12_12") (pintype "bidirectional"))
      (node (ref "U1") (pin "P$K2") (pinfunction "P0.05/AIN3_P$K2") (pintype "bidirectional"))
    )
    (net (code "16") (name "EPD_DC") (class "Default")
      (node (ref "J1") (pin "11") (pinfunction "11_11") (pintype "bidirectional"))
      (node (ref "U1") (pin "P$AD10") (pinfunction "P0.15_P$AD10") (pintype "bidirectional"))
    )
    (net (code "17") (name "EPD_RST") (class "Default")
      (node (ref "J1") (pin "10") (pinfunction "10_10") (pintype "bidirectional"))
      (node (ref "U1") (pin "P$AC11") (pinfunction "P0.16_P$AC11") (pintype "bidirectional"))
    )
    (net (code "18") (name "GDR") (class "Default")
      (node (ref "J1") (pin "2") (pinfunction "2_2") (pintype "bidirectional"))
      (node (ref "Q3") (pin "1") (pinfunction "G_1") (pintype "bidirectional"))
      (node (ref "R2_EP_DR") (pin "2") (pinfunction "2_2") (pintype "bidirectional"))
    )
    (net (code "19") (name "GND") (class "Default")
      (node (ref "C1") (pin "2") (pinfunction "2_2") (pintype "passive"))
      (node (ref "C1-EP-DR") (pin "2") (pinfunction "2_2") (pintype "passive"))
      (node (ref "C10") (pin "2") (pinfunction "2_2") (pintype "passive"))
      (node (ref "C11") (pin "2") (pinfunction "2_2") (pintype "passive"))
      (node (ref "C12") (pin "2") (pinfunction "2_2") (pintype "passive"))
      (node (ref "C13") (pin "2") (pinfunction "2_2") (pintype "passive"))
      (node (ref "C14") (pin "2") (pinfunction "2_2") (pintype "passive"))
      (node (ref "C15") (pin "2") (pinfunction "2_2") (pintype "passive"))
      (node (ref "C16") (pin "2") (pinfunction "2_2") (pintype "passive"))
      (node (ref "C17") (pin "1") (pinfunction "1_1") (pintype "passive"))
      (node (ref "C18") (pin "1") (pinfunction "1_1") (pintype "passive"))
      (node (ref "C19") (pin "2") (pinfunction "2_2") (pintype "passive"))
      (node (ref "C2") (pin "2") (pinfunction "2_2") (pintype "passive"))
      (node (ref "C20") (pin "2") (pinfunction "2_2") (pintype "passive"))
      (node (ref "C21") (pin "2") (pinfunction "2_2") (pintype "passive"))
      (node (ref "C22") (pin "2") (pinfunction "2_2") (pintype "passive"))
      (node (ref "C23") (pin "1") (pinfunction "1_1") (pintype "passive"))
      (node (ref "C24") (pin "1") (pinfunction "1_1") (pintype "passive"))
      (node (ref "C25") (pin "2") (pinfunction "2_2") (pintype "passive"))
      (node (ref "C27") (pin "1") (pinfunction "1_1") (pintype "passive"))
      (node (ref "C29") (pin "1") (pinfunction "1_1") (pintype "passive"))
      (node (ref "C3") (pin "2") (pinfunction "2_2") (pintype "passive"))
      (node (ref "C30") (pin "1") (pinfunction "1_1") (pintype "passive"))
      (node (ref "C31") (pin "1") (pinfunction "1_1") (pintype "passive"))
      (node (ref "C32") (pin "1") (pinfunction "1_1") (pintype "passive"))
      (node (ref "C33") (pin "2") (pinfunction "2_2") (pintype "passive"))
      (node (ref "C34") (pin "1") (pinfunction "1_1") (pintype "passive"))
      (node (ref "C37") (pin "1") (pinfunction "1_1") (pintype "passive"))
      (node (ref "C38") (pin "1") (pinfunction "1_1") (pintype "passive"))
      (node (ref "C39") (pin "2") (pinfunction "2_2") (pintype "passive"))
      (node (ref "C4") (pin "2") (pinfunction "2_2") (pintype "passive"))
      (node (ref "C42") (pin "2") (pinfunction "2_2") (pintype "passive"))
      (node (ref "C43") (pin "2") (pinfunction "2_2") (pintype "passive"))
      (node (ref "C5") (pin "2") (pinfunction "2_2") (pintype "passive"))
      (node (ref "C6") (pin "2") (pinfunction "2_2") (pintype "passive"))
      (node (ref "C7") (pin "2") (pinfunction "2_2") (pintype "passive"))
      (node (ref "C8") (pin "2") (pinfunction "2_2") (pintype "passive"))
      (node (ref "C9") (pin "2") (pinfunction "2_2") (pintype "passive"))
      (node (ref "D3") (pin "2") (pinfunction "GND_2") (pintype "bidirectional"))
      (node (ref "D4") (pin "1") (pinfunction "K_1") (pintype "bidirectional"))
      (node (ref "EPD_C1") (pin "1") (pinfunction "1_1") (pintype "passive"))
      (node (ref "EPD_C10") (pin "1") (pinfunction "1_1") (pintype "passive"))
      (node (ref "EPD_C11") (pin "1") (pinfunction "1_1") (pintype "passive"))
      (node (ref "EPD_C12") (pin "1") (pinfunction "1_1") (pintype "passive"))
      (node (ref "EPD_C2") (pin "1") (pinfunction "1_1") (pintype "passive"))
      (node (ref "EPD_C5") (pin "1") (pinfunction "1_1") (pintype "passive"))
      (node (ref "EPD_C6") (pin "1") (pinfunction "1_1") (pintype "passive"))
      (node (ref "EPD_C7") (pin "1") (pinfunction "1_1") (pintype "passive"))
      (node (ref "EPD_C8") (pin "1") (pinfunction "1_1") (pintype "passive"))
      (node (ref "EPD_C9") (pin "1") (pinfunction "1_1") (pintype "passive"))
      (node (ref "IC1") (pin "D2") (pinfunction "GND_D2") (pintype "bidirectional"))
      (node (ref "IC2") (pin "B1") (pinfunction "IN/TRIG_B1") (pintype "bidirectional"))
      (node (ref "IC2") (pin "B3") (pinfunction "GND_B3") (pintype "bidirectional"))
      (node (ref "IC3") (pin "8") (pinfunction "GNDIO_8") (pintype "bidirectional"))
      (node (ref "IC3") (pin "9") (pinfunction "GND_9") (pintype "bidirectional"))
      (node (ref "IC9") (pin "B1") (pinfunction "VSEL_B1") (pintype "bidirectional"))
      (node (ref "IC9") (pin "C1") (pinfunction "AGND_C1") (pintype "bidirectional"))
      (node (ref "IC9") (pin "C2") (pinfunction "PGND_1_C2") (pintype "bidirectional"))
      (node (ref "IC9") (pin "C3") (pinfunction "PGND_2_C3") (pintype "bidirectional"))
      (node (ref "J1") (pin "17") (pinfunction "17_17") (pintype "bidirectional"))
      (node (ref "J1") (pin "8") (pinfunction "8_8") (pintype "bidirectional"))
      (node (ref "J1") (pin "MP1") (pinfunction "MP1_MP1") (pintype "bidirectional"))
      (node (ref "J1") (pin "MP2") (pinfunction "MP2_MP2") (pintype "bidirectional"))
      (node (ref "J2") (pin "3") (pinfunction "3_3") (pintype "bidirectional"))
      (node (ref "J2") (pin "5") (pinfunction "5_5") (pintype "bidirectional"))
      (node (ref "J4") (pin "A12_B1") (pinfunction "GND_A12_B1") (pintype "power_in"))
      (node (ref "J4") (pin "A1_B12") (pinfunction "GND_A1_B12") (pintype "power_in"))
      (node (ref "J4") (pin "SH1") (pinfunction "SHIELD_SH1") (pintype "passive"))
      (node (ref "J4") (pin "SH2") (pinfunction "SHIELD_SH2") (pintype "passive"))
      (node (ref "J4") (pin "SH3") (pinfunction "SHIELD_SH3") (pintype "passive"))
      (node (ref "J4") (pin "SH4") (pinfunction "SHIELD_SH4") (pintype "passive"))
      (node (ref "R1_USB") (pin "1") (pinfunction "1_1") (pintype "bidirectional"))
      (node (ref "R2_EP_DR") (pin "1") (pinfunction "1_1") (pintype "bidirectional"))
      (node (ref "R2_USB") (pin "2") (pinfunction "2_2") (pintype "bidirectional"))
      (node (ref "R3") (pin "1") (pinfunction "1_1") (pintype "bidirectional"))
      (node (ref "R9") (pin "1") (pinfunction "1_1") (pintype "bidirectional"))
      (node (ref "R_TYPE_SEL") (pin "1") (pinfunction "1_1") (pintype "bidirectional"))
      (node (ref "SJ1") (pin "1") (pinfunction "1_1") (pintype "passive"))
      (node (ref "SW_DN") (pin "1") (pinfunction "1_1") (pintype "passive"))
      (node (ref "SW_ENT") (pin "1") (pinfunction "1_1") (pintype "passive"))
      (node (ref "SW_UP") (pin "1") (pinfunction "1_1") (pintype "passive"))
      (node (ref "TP_BAT_GND") (pin "TP") (pinfunction "TP_TP") (pintype "input"))
      (node (ref "TP_GND") (pin "TP") (pinfunction "TP_TP") (pintype "input"))
      (node (ref "U1") (pin "P$74") (pinfunction "VSS_PAD_P$74") (pintype "bidirectional"))
      (node (ref "U1") (pin "P$75") (pinfunction "VSS_PAD_P$75") (pintype "bidirectional"))
      (node (ref "U1") (pin "P$76") (pinfunction "VSS_PAD_P$76") (pintype "bidirectional"))
      (node (ref "U1") (pin "P$77") (pinfunction "VSS_PAD_P$77") (pintype "bidirectional"))
      (node (ref "U1") (pin "P$78") (pinfunction "VSS_PAD_P$78") (pintype "bidirectional"))
      (node (ref "U1") (pin "P$79") (pinfunction "VSS_PAD_P$79") (pintype "bidirectional"))
      (node (ref "U1") (pin "P$80") (pinfunction "VSS_PAD_P$80") (pintype "bidirectional"))
      (node (ref "U1") (pin "P$81") (pinfunction "VSS_PAD_P$81") (pintype "bidirectional"))
      (node (ref "U1") (pin "P$82") (pinfunction "VSS_PAD_P$82") (pintype "bidirectional"))
      (node (ref "U1") (pin "P$83") (pinfunction "VSS_PAD_P$83") (pintype "bidirectional"))
      (node (ref "U1") (pin "P$84") (pinfunction "VSS_PAD_P$84") (pintype "bidirectional"))
      (node (ref "U1") (pin "P$85") (pinfunction "VSS_PAD_P$85") (pintype "bidirectional"))
      (node (ref "U1") (pin "P$86") (pinfunction "VSS_PAD_P$86") (pintype "bidirectional"))
      (node (ref "U1") (pin "P$87") (pinfunction "VSS_PAD_P$87") (pintype "bidirectional"))
      (node (ref "U1") (pin "P$88") (pinfunction "VSS_PAD_P$88") (pintype "bidirectional"))
      (node (ref "U1") (pin "P$89") (pinfunction "VSS_PAD_P$89") (pintype "bidirectional"))
      (node (ref "U1") (pin "P$90") (pinfunction "VSS_PAD_P$90") (pintype "bidirectional"))
      (node (ref "U1") (pin "P$B7") (pinfunction "VSS_P$B7") (pintype "power_in"))
      (node (ref "U1") (pin "P$F23") (pinfunction "VSS_PA_P$F23") (pintype "bidirectional"))
      (node (ref "U3") (pin "1") (pinfunction "CTG_1") (pintype "power_in"))
      (node (ref "U3") (pin "4") (pinfunction "GND_4") (pintype "power_in"))
      (node (ref "U3") (pin "6") (pinfunction "QSTRT_6") (pintype "input"))
      (node (ref "U3") (pin "9") (pinfunction "EP_9") (pintype "power_in"))
      (node (ref "X1") (pin "2") (pinfunction "2_2") (pintype "passive"))
      (node (ref "X1") (pin "4") (pinfunction "4_4") (pintype "passive"))
    )
    (net (code "20") (name "HAPTIC_EN") (class "Default")
      (node (ref "IC2") (pin "A1") (pinfunction "EN_A1") (pintype "bidirectional"))
      (node (ref "U1") (pin "P$U1") (pinfunction "P0.12_P$U1") (pintype "bidirectional"))
    )
    (net (code "21") (name "IMU_INT1") (class "Default")
      (node (ref "IC3") (pin "5") (pinfunction "INT1_5") (pintype "bidirectional"))
      (node (ref "U1") (pin "P$N1") (pinfunction "P0.08_P$N1") (pintype "bidirectional"))
    )
    (net (code "22") (name "IMU_INT2") (class "Default")
      (node (ref "IC3") (pin "6") (pinfunction "INT2_6") (pintype "bidirectional"))
      (node (ref "U1") (pin "P$P2") (pinfunction "P1.08_P$P2") (pintype "bidirectional"))
    )
    (net (code "23") (name "LX1") (class "Default")
      (node (ref "IC9") (pin "B2") (pinfunction "SW1_1_B2") (pintype "bidirectional"))
      (node (ref "IC9") (pin "B3") (pinfunction "SW1_2_B3") (pintype "bidirectional"))
      (node (ref "L7") (pin "1") (pinfunction "1_1") (pintype "bidirectional"))
    )
    (net (code "24") (name "LX2") (class "Default")
      (node (ref "IC9") (pin "D2") (pinfunction "SW2_1_D2") (pintype "bidirectional"))
      (node (ref "IC9") (pin "D3") (pinfunction "SW2_2_D3") (pintype "bidirectional"))
      (node (ref "L7") (pin "2") (pinfunction "2_2") (pintype "bidirectional"))
    )
    (net (code "25") (name "MOSI") (class "Default")
      (node (ref "J1") (pin "14") (pinfunction "14_14") (pintype "bidirectional"))
      (node (ref "U1") (pin "P$B13") (pinfunction "P0.03/AIN1_P$B13") (pintype "bidirectional"))
    )
    (net (code "26") (name "Net-(D2-K)") (class "Default")
      (node (ref "C2-EP-DR") (pin "1") (pinfunction "1_1") (pintype "passive"))
      (node (ref "D2") (pin "1") (pinfunction "K_1") (pintype "bidirectional"))
      (node (ref "D4") (pin "2") (pinfunction "A_2") (pintype "bidirectional"))
    )
    (net (code "27") (name "Net-(D5-A)") (class "Default")
      (node (ref "C2-EP-DR") (pin "2") (pinfunction "2_2") (pintype "passive"))
      (node (ref "D5") (pin "2") (pinfunction "A_2") (pintype "bidirectional"))
      (node (ref "L5") (pin "1") (pinfunction "1_1") (pintype "passive"))
      (node (ref "Q3") (pin "3") (pinfunction "D_3") (pintype "bidirectional"))
    )
    (net (code "28") (name "Net-(EPD_C1-Pad2)") (class "Default")
      (node (ref "EPD_C1") (pin "2") (pinfunction "2_2") (pintype "passive"))
      (node (ref "J1") (pin "5") (pinfunction "5_5") (pintype "bidirectional"))
    )
    (net (code "29") (name "Net-(EPD_C2-Pad2)") (class "Default")
      (node (ref "EPD_C2") (pin "2") (pinfunction "2_2") (pintype "passive"))
      (node (ref "J1") (pin "4") (pinfunction "4_4") (pintype "bidirectional"))
    )
    (net (code "30") (name "Net-(EPD_C6-Pad2)") (class "Default")
      (node (ref "EPD_C6") (pin "2") (pinfunction "2_2") (pintype "passive"))
      (node (ref "J1") (pin "18") (pinfunction "18_18") (pintype "bidirectional"))
    )
    (net (code "31") (name "Net-(EPD_C7-Pad2)") (class "Default")
      (node (ref "EPD_C7") (pin "2") (pinfunction "2_2") (pintype "passive"))
      (node (ref "J1") (pin "19") (pinfunction "19_19") (pintype "bidirectional"))
    )
    (net (code "32") (name "Net-(EPD_C8-Pad2)") (class "Default")
      (node (ref "EPD_C8") (pin "2") (pinfunction "2_2") (pintype "passive"))
      (node (ref "J1") (pin "20") (pinfunction "20_20") (pintype "bidirectional"))
    )
    (net (code "33") (name "Net-(EPD_C10-Pad2)") (class "Default")
      (node (ref "EPD_C10") (pin "2") (pinfunction "2_2") (pintype "passive"))
      (node (ref "J1") (pin "22") (pinfunction "22_22") (pintype "bidirectional"))
    )
    (net (code "34") (name "Net-(EPD_C12-Pad2)") (class "Default")
      (node (ref "EPD_C12") (pin "2") (pinfunction "2_2") (pintype "passive"))
      (node (ref "J1") (pin "24") (pinfunction "24_24") (pintype "bidirectional"))
    )
    (net (code "35") (name "Net-(IC1-TS{slash}MR)") (class "Default")
      (node (ref "IC1") (pin "D1") (pinfunction "TS/MR_D1") (pintype "bidirectional"))
      (node (ref "R9") (pin "2") (pinfunction "2_2") (pintype "bidirectional"))
    )
    (net (code "36") (name "Net-(IC2-REG)") (class "Default")
      (node (ref "C32") (pin "2") (pinfunction "2_2") (pintype "passive"))
      (node (ref "IC2") (pin "A2") (pinfunction "REG_A2") (pintype "bidirectional"))
    )
    (net (code "37") (name "Net-(IC3-SDO)") (class "Default")
      (node (ref "IC3") (pin "1") (pinfunction "SDO_1") (pintype "bidirectional"))
      (node (ref "R3") (pin "2") (pinfunction "2_2") (pintype "bidirectional"))
    )
    (net (code "38") (name "Net-(IC9-SCL)") (class "Default")
      (node (ref "IC9") (pin "D1") (pinfunction "SCL_D1") (pintype "bidirectional"))
      (node (ref "R4") (pin "2") (pinfunction "2_2") (pintype "bidirectional"))
    )
    (net (code "39") (name "Net-(IC9-SDA)") (class "Default")
      (node (ref "IC9") (pin "E1") (pinfunction "SDA_E1") (pintype "bidirectional"))
      (node (ref "R2") (pin "2") (pinfunction "2_2") (pintype "bidirectional"))
    )
    (net (code "40") (name "Net-(J4-CC1)") (class "Default")
      (node (ref "J4") (pin "A5") (pinfunction "CC1_A5") (pintype "bidirectional"))
      (node (ref "R1_USB") (pin "2") (pinfunction "2_2") (pintype "bidirectional"))
    )
    (net (code "41") (name "Net-(J4-CC2)") (class "Default")
      (node (ref "J4") (pin "B5") (pinfunction "CC2_B5") (pintype "bidirectional"))
      (node (ref "R2_USB") (pin "1") (pinfunction "1_1") (pintype "bidirectional"))
    )
    (net (code "42") (name "Net-(L2-Pad2)") (class "Default")
      (node (ref "L2") (pin "2") (pinfunction "2_2") (pintype "passive"))
      (node (ref "L3") (pin "1") (pinfunction "1_1") (pintype "passive"))
    )
    (net (code "43") (name "Net-(R1_EP_DR-Pad1)") (class "Default")
      (node (ref "R1_EP_DR") (pin "1") (pinfunction "1_1") (pintype "bidirectional"))
      (node (ref "R_TYPE_SEL") (pin "2") (pinfunction "2_2") (pintype "bidirectional"))
      (node (ref "SJ1") (pin "2") (pinfunction "2_2") (pintype "passive"))
    )
    (net (code "44") (name "Net-(R5-Pad2)") (class "Default")
      (node (ref "R5") (pin "2") (pinfunction "2_2") (pintype "bidirectional"))
      (node (ref "R7") (pin "2") (pinfunction "2_2") (pintype "bidirectional"))
      (node (ref "R8") (pin "2") (pinfunction "2_2") (pintype "bidirectional"))
    )
    (net (code "45") (name "Net-(U1-ANT)") (class "Default")
      (node (ref "C3") (pin "1") (pinfunction "1_1") (pintype "passive"))
      (node (ref "L1") (pin "1") (pinfunction "1_1") (pintype "passive"))
      (node (ref "U1") (pin "P$H23") (pinfunction "ANT_P$H23") (pintype "bidirectional"))
    )
    (net (code "46") (name "Net-(U1-DCC)") (class "Default")
      (node (ref "L2") (pin "1") (pinfunction "1_1") (pintype "passive"))
      (node (ref "U1") (pin "P$B3") (pinfunction "DCC_P$B3") (pintype "output"))
    )
    (net (code "47") (name "Net-(U1-DEC2)") (class "Default")
      (node (ref "C13") (pin "1") (pinfunction "1_1") (pintype "passive"))
      (node (ref "U1") (pin "P$A18") (pinfunction "DEC2_P$A18") (pintype "bidirectional"))
    )
    (net (code "48") (name "Net-(U1-DEC3V3)") (class "Default")
      (node (ref "C20") (pin "1") (pinfunction "1_1") (pintype "passive"))
      (node (ref "U1") (pin "P$AC5") (pinfunction "DEC3V3_P$AC5") (pintype "bidirectional"))
    )
    (net (code "49") (name "Net-(U1-DEC5)") (class "Default")
      (node (ref "C9") (pin "1") (pinfunction "1_1") (pintype "passive"))
      (node (ref "U1") (pin "P$N24") (pinfunction "DEC5_P$N24") (pintype "bidirectional"))
    )
    (net (code "50") (name "Net-(U1-XC1)") (class "Default")
      (node (ref "C1") (pin "1") (pinfunction "1_1") (pintype "passive"))
      (node (ref "U1") (pin "P$B24") (pinfunction "XC1_P$B24") (pintype "input"))
      (node (ref "X1") (pin "1") (pinfunction "1_1") (pintype "passive"))
    )
    (net (code "51") (name "Net-(U1-XC2)") (class "Default")
      (node (ref "C2") (pin "1") (pinfunction "1_1") (pintype "passive"))
      (node (ref "U1") (pin "P$A23") (pinfunction "XC2_P$A23") (pintype "output"))
      (node (ref "X1") (pin "3") (pinfunction "3_3") (pintype "passive"))
    )
    (net (code "52") (name "OUT+") (class "Default")
      (node (ref "IC2") (pin "A3") (pinfunction "OUT+_A3") (pintype "bidirectional"))
      (node (ref "TP1") (pin "TP") (pinfunction "TP_TP") (pintype "input"))
    )
    (net (code "53") (name "OUT-") (class "Default")
      (node (ref "IC2") (pin "C3") (pinfunction "OUT-_C3") (pintype "bidirectional"))
      (node (ref "TP2") (pin "TP") (pinfunction "TP_TP") (pintype "input"))
    )
    (net (code "54") (name "P0.04") (class "Default")
      (node (ref "U1") (pin "P$J1") (pinfunction "P0.04/AIN2_P$J1") (pintype "bidirectional"))
    )
    (net (code "55") (name "P0.09") (class "Default")
      (node (ref "U1") (pin "P$L24") (pinfunction "P0.09/NFC1_P$L24") (pintype "bidirectional"))
    )
    (net (code "56") (name "P0.13") (class "Default")
      (node (ref "C30") (pin "2") (pinfunction "2_2") (pintype "passive"))
      (node (ref "R5") (pin "1") (pinfunction "1_1") (pintype "bidirectional"))
      (node (ref "SW_UP") (pin "2") (pinfunction "2_2") (pintype "passive"))
      (node (ref "U1") (pin "P$AD8") (pinfunction "P0.13_P$AD8") (pintype "bidirectional"))
    )
    (net (code "57") (name "P0.14") (class "Default")
      (node (ref "C31") (pin "2") (pinfunction "2_2") (pintype "passive"))
      (node (ref "R8") (pin "1") (pinfunction "1_1") (pintype "bidirectional"))
      (node (ref "SW_ENT") (pin "2") (pinfunction "2_2") (pintype "passive"))
      (node (ref "U1") (pin "P$AC9") (pinfunction "P0.14_P$AC9") (pintype "bidirectional"))
    )
    (net (code "58") (name "P0.19") (class "Default")
      (node (ref "U1") (pin "P$AC15") (pinfunction "P0.19_P$AC15") (pintype "bidirectional"))
    )
    (net (code "59") (name "P0.20") (class "Default")
      (node (ref "U1") (pin "P$AD16") (pinfunction "P0.20_P$AD16") (pintype "bidirectional"))
    )
    (net (code "60") (name "P0.21") (class "Default")
      (node (ref "U1") (pin "P$AC17") (pinfunction "P0.21_P$AC17") (pintype "bidirectional"))
    )
    (net (code "61") (name "P0.22") (class "Default")
      (node (ref "U1") (pin "P$AD18") (pinfunction "P0.22_P$AD18") (pintype "bidirectional"))
    )
    (net (code "62") (name "P0.23") (class "Default")
      (node (ref "U1") (pin "P$AC19") (pinfunction "P0.23_P$AC19") (pintype "bidirectional"))
    )
    (net (code "63") (name "P0.24") (class "Default")
      (node (ref "U1") (pin "P$AD20") (pinfunction "P0.24_P$AD20") (pintype "bidirectional"))
    )
    (net (code "64") (name "P0.25") (class "Default")
      (node (ref "U1") (pin "P$AC21") (pinfunction "P0.25_P$AC21") (pintype "bidirectional"))
    )
    (net (code "65") (name "P0.26") (class "Default")
      (node (ref "U1") (pin "P$G1") (pinfunction "P0.26_P$G1") (pintype "bidirectional"))
    )
    (net (code "66") (name "P0.27") (class "Default")
      (node (ref "U1") (pin "P$H2") (pinfunction "P0.27_P$H2") (pintype "bidirectional"))
    )
    (net (code "67") (name "P0.28") (class "Default")
      (node (ref "U1") (pin "P$B11") (pinfunction "P0.28/AIN4_P$B11") (pintype "bidirectional"))
    )
    (net (code "68") (name "P0.29") (class "Default")
      (node (ref "U1") (pin "P$A10") (pinfunction "P0.29/AIN5_P$A10") (pintype "bidirectional"))
    )
    (net (code "69") (name "P0.30") (class "Default")
      (node (ref "U1") (pin "P$B9") (pinfunction "P0.30/AIN6_P$B9") (pintype "bidirectional"))
    )
    (net (code "70") (name "P0.31") (class "Default")
      (node (ref "U1") (pin "P$A8") (pinfunction "P0.31/AIN7_P$A8") (pintype "bidirectional"))
    )
    (net (code "71") (name "P1.01") (class "Default")
      (node (ref "Q1") (pin "1") (pinfunction "G_1") (pintype "bidirectional"))
      (node (ref "R_PWR_EPD") (pin "1") (pinfunction "1_1") (pintype "bidirectional"))
      (node (ref "U1") (pin "P$Y23") (pinfunction "P1.01_P$Y23") (pintype "bidirectional"))
    )
    (net (code "72") (name "P1.02") (class "Default")
      (node (ref "C29") (pin "2") (pinfunction "2_2") (pintype "passive"))
      (node (ref "R7") (pin "1") (pinfunction "1_1") (pintype "bidirectional"))
      (node (ref "SW_DN") (pin "2") (pinfunction "2_2") (pintype "passive"))
      (node (ref "U1") (pin "P$W24") (pinfunction "P1.02_P$W24") (pintype "bidirectional"))
    )
    (net (code "73") (name "P1.03") (class "Default")
      (node (ref "U1") (pin "P$V23") (pinfunction "P1.03_P$V23") (pintype "bidirectional"))
    )
    (net (code "74") (name "P1.04") (class "Default")
      (node (ref "U1") (pin "P$U24") (pinfunction "P1.04_P$U24") (pintype "bidirectional"))
    )
    (net (code "75") (name "P1.05") (class "Default")
      (node (ref "U1") (pin "P$T23") (pinfunction "P1.05_P$T23") (pintype "bidirectional"))
    )
    (net (code "76") (name "P1.06") (class "Default")
      (node (ref "U1") (pin "P$R24") (pinfunction "P1.06_P$R24") (pintype "bidirectional"))
    )
    (net (code "77") (name "P1.07") (class "Default")
      (node (ref "U1") (pin "P$P23") (pinfunction "P1.07_P$P23") (pintype "bidirectional"))
    )
    (net (code "78") (name "P1.09") (class "Default")
      (node (ref "U1") (pin "P$R1") (pinfunction "P1.09_P$R1") (pintype "bidirectional"))
    )
    (net (code "79") (name "P1.10") (class "Default")
      (node (ref "U1") (pin "P$A20") (pinfunction "P1.10_P$A20") (pintype "bidirectional"))
    )
    (net (code "80") (name "P1.11") (class "Default")
      (node (ref "U1") (pin "P$B19") (pinfunction "P1.11_P$B19") (pintype "bidirectional"))
    )
    (net (code "81") (name "P1.12") (class "Default")
      (node (ref "U1") (pin "P$B17") (pinfunction "P1.12_P$B17") (pintype "bidirectional"))
    )
    (net (code "82") (name "P1.13") (class "Default")
      (node (ref "U1") (pin "P$A16") (pinfunction "P1.13_P$A16") (pintype "bidirectional"))
    )
    (net (code "83") (name "P1.14") (class "Default")
      (node (ref "U1") (pin "P$B15") (pinfunction "P1.14_P$B15") (pintype "bidirectional"))
    )
    (net (code "84") (name "P1.15") (class "Default")
      (node (ref "U1") (pin "P$A14") (pinfunction "P1.15_P$A14") (pintype "bidirectional"))
    )
    (net (code "85") (name "PMIC_INT") (class "Default")
      (node (ref "IC1") (pin "A1") (pinfunction "~{INT}_A1") (pintype "bidirectional"))
      (node (ref "U1") (pin "P$T2") (pinfunction "P0.11_P$T2") (pintype "bidirectional"))
    )
    (net (code "86") (name "PREVGH") (class "Default")
      (node (ref "D5") (pin "1") (pinfunction "K_1") (pintype "bidirectional"))
      (node (ref "EPD_C9") (pin "2") (pinfunction "2_2") (pintype "passive"))
      (node (ref "J1") (pin "21") (pinfunction "21_21") (pintype "bidirectional"))
    )
    (net (code "87") (name "PREVGL") (class "Default")
      (node (ref "D2") (pin "2") (pinfunction "A_2") (pintype "bidirectional"))
      (node (ref "EPD_C11") (pin "2") (pinfunction "2_2") (pintype "passive"))
      (node (ref "J1") (pin "23") (pinfunction "23_23") (pintype "bidirectional"))
    )
    (net (code "88") (name "RESE") (class "Default")
      (node (ref "J1") (pin "3") (pinfunction "3_3") (pintype "bidirectional"))
      (node (ref "Q3") (pin "2") (pinfunction "S_2") (pintype "bidirectional"))
      (node (ref "R1_EP_DR") (pin "2") (pinfunction "2_2") (pintype "bidirectional"))
    )
    (net (code "89") (name "RESET") (class "Default")
      (node (ref "J2") (pin "6") (pinfunction "6_6") (pintype "bidirectional"))
      (node (ref "TP_RESET") (pin "TP") (pinfunction "TP_TP") (pintype "input"))
      (node (ref "U1") (pin "P$AC13") (pinfunction "P0.18/RESET_P$AC13") (pintype "bidirectional"))
    )
    (net (code "90") (name "SCK") (class "Default")
      (node (ref "J1") (pin "13") (pinfunction "13_13") (pintype "bidirectional"))
      (node (ref "U1") (pin "P$A12") (pinfunction "P0.02/AIN0_P$A12") (pintype "bidirectional"))
    )
    (net (code "91") (name "SCL") (class "Default")
      (node (ref "IC1") (pin "B1") (pinfunction "SCL_B1") (pintype "bidirectional"))
      (node (ref "IC2") (pin "C1") (pinfunction "SCL_C1") (pintype "bidirectional"))
      (node (ref "IC3") (pin "12") (pinfunction "SCX_12") (pintype "bidirectional"))
      (node (ref "R17") (pin "2") (pinfunction "2_2") (pintype "bidirectional"))
      (node (ref "R4") (pin "1") (pinfunction "1_1") (pintype "bidirectional"))
      (node (ref "TP_SCL") (pin "TP") (pinfunction "TP_TP") (pintype "input"))
      (node (ref "U1") (pin "P$M2") (pinfunction "P0.07_P$M2") (pintype "bidirectional"))
      (node (ref "U3") (pin "7") (pinfunction "SCL_7") (pintype "input"))
    )
    (net (code "92") (name "SDA") (class "Default")
      (node (ref "IC1") (pin "C1") (pinfunction "SDA_C1") (pintype "bidirectional"))
      (node (ref "IC2") (pin "B2") (pinfunction "SDA_B2") (pintype "bidirectional"))
      (node (ref "IC3") (pin "2") (pinfunction "SDX_2") (pintype "bidirectional"))
      (node (ref "R18") (pin "2") (pinfunction "2_2") (pintype "bidirectional"))
      (node (ref "R2") (pin "1") (pinfunction "1_1") (pintype "bidirectional"))
      (node (ref "TP_SDA") (pin "TP") (pinfunction "TP_TP") (pintype "input"))
      (node (ref "U1") (pin "P$L1") (pinfunction "P0.06_P$L1") (pintype "bidirectional"))
      (node (ref "U3") (pin "8") (pinfunction "SDA_8") (pintype "bidirectional"))
    )
    (net (code "93") (name "SWDCLK") (class "Default")
      (node (ref "J2") (pin "4") (pinfunction "4_4") (pintype "bidirectional"))
      (node (ref "TP_SWDCLK") (pin "TP") (pinfunction "TP_TP") (pintype "input"))
      (node (ref "U1") (pin "P$AA24") (pinfunction "SWDCLK_P$AA24") (pintype "input"))
    )
    (net (code "94") (name "SWDIO") (class "Default")
      (node (ref "J2") (pin "2") (pinfunction "2_2") (pintype "bidirectional"))
      (node (ref "TP_SWDIO") (pin "TP") (pinfunction "TP_TP") (pintype "input"))
      (node (ref "U1") (pin "P$AC24") (pinfunction "SWDIO_P$AC24") (pintype "bidirectional"))
    )
    (net (code "95") (name "SWO") (class "Default")
      (node (ref "TP_SWO") (pin "TP") (pinfunction "TP_TP") (pintype "input"))
      (node (ref "U1") (pin "P$AD22") (pinfunction "P1.00_P$AD22") (pintype "bidirectional"))
    )
    (net (code "96") (name "VBAT") (class "Default")
      (node (ref "C27") (pin "2") (pinfunction "2_2") (pintype "passive"))
      (node (ref "C37") (pin "2") (pinfunction "2_2") (pintype "passive"))
      (node (ref "IC1") (pin "C2") (pinfunction "BAT_C2") (pintype "bidirectional"))
      (node (ref "TP_VBAT") (pin "TP") (pinfunction "TP_TP") (pintype "input"))
      (node (ref "U3") (pin "2") (pinfunction "CELL_2") (pintype "power_in"))
      (node (ref "U3") (pin "3") (pinfunction "VDD_3") (pintype "power_in"))
    )
    (net (code "97") (name "VBUS") (class "Default")
      (node (ref "C21") (pin "1") (pinfunction "1_1") (pintype "passive"))
      (node (ref "C38") (pin "2") (pinfunction "2_2") (pintype "passive"))
      (node (ref "C42") (pin "1") (pinfunction "1_1") (pintype "passive"))
      (node (ref "C43") (pin "1") (pinfunction "1_1") (pintype "passive"))
      (node (ref "D3") (pin "5") (pinfunction "VBUS_5") (pintype "bidirectional"))
      (node (ref "IC1") (pin "A2") (pinfunction "IN_A2") (pintype "bidirectional"))
      (node (ref "J4") (pin "A4_B9") (pinfunction "VBUS_A4_B9") (pintype "power_in"))
      (node (ref "J4") (pin "A9_B4") (pinfunction "VBUS_A9_B4") (pintype "power_in"))
      (node (ref "U1") (pin "P$AD2") (pinfunction "VBUS_P$AD2") (pintype "power_in"))
    )
    (net (code "98") (name "VREG") (class "Default")
      (node (ref "C23") (pin "2") (pinfunction "2_2") (pintype "passive"))
      (node (ref "C24") (pin "2") (pinfunction "2_2") (pintype "passive"))
      (node (ref "C39") (pin "1") (pinfunction "1_1") (pintype "passive"))
      (node (ref "IC1") (pin "B2") (pinfunction "SYS_B2") (pintype "bidirectional"))
      (node (ref "IC9") (pin "A1") (pinfunction "EN_A1") (pintype "bidirectional"))
      (node (ref "IC9") (pin "A2") (pinfunction "VIN_1_A2") (pintype "bidirectional"))
      (node (ref "IC9") (pin "A3") (pinfunction "VIN_2_A3") (pintype "bidirectional"))
      (node (ref "TP_VREG") (pin "TP") (pinfunction "TP_TP") (pintype "input"))
    )
    (net (code "99") (name "unconnected-(ANT1-NC-Pad2)") (class "Default")
      (node (ref "ANT1") (pin "2") (pinfunction "NC_2") (pintype "no_connect"))
    )
    (net (code "100") (name "unconnected-(IC3-ASCL-Pad11)") (class "Default")
      (node (ref "IC3") (pin "11") (pinfunction "ASCL_11") (pintype "bidirectional"))
    )
    (net (code "101") (name "unconnected-(IC3-ASDA-Pad4)") (class "Default")
      (node (ref "IC3") (pin "4") (pinfunction "ASDA_4") (pintype "bidirectional"))
    )
    (net (code "102") (name "unconnected-(J1-Pad1)") (class "Default")
      (node (ref "J1") (pin "1") (pinfunction "1_1") (pintype "bidirectional"))
    )
    (net (code "103") (name "unconnected-(J1-Pad6)") (class "Default")
      (node (ref "J1") (pin "6") (pinfunction "6_6") (pintype "bidirectional"))
    )
    (net (code "104") (name "unconnected-(J1-Pad7)") (class "Default")
      (node (ref "J1") (pin "7") (pinfunction "7_7") (pintype "bidirectional"))
    )
    (net (code "105") (name "unconnected-(J4-SBU1-PadA8)") (class "Default")
      (node (ref "J4") (pin "A8") (pinfunction "SBU1_A8") (pintype "bidirectional"))
    )
    (net (code "106") (name "unconnected-(J4-SBU2-PadB8)") (class "Default")
      (node (ref "J4") (pin "B8") (pinfunction "SBU2_B8") (pintype "bidirectional"))
    )
    (net (code "107") (name "unconnected-(U1-DCCH-PadP$AB2)") (class "Default")
      (node (ref "U1") (pin "P$AB2") (pinfunction "DCCH_P$AB2") (pintype "bidirectional"))
    )
  )
)
